# untitled.net
KiCad netlist of a schematic drawn in EAGLE
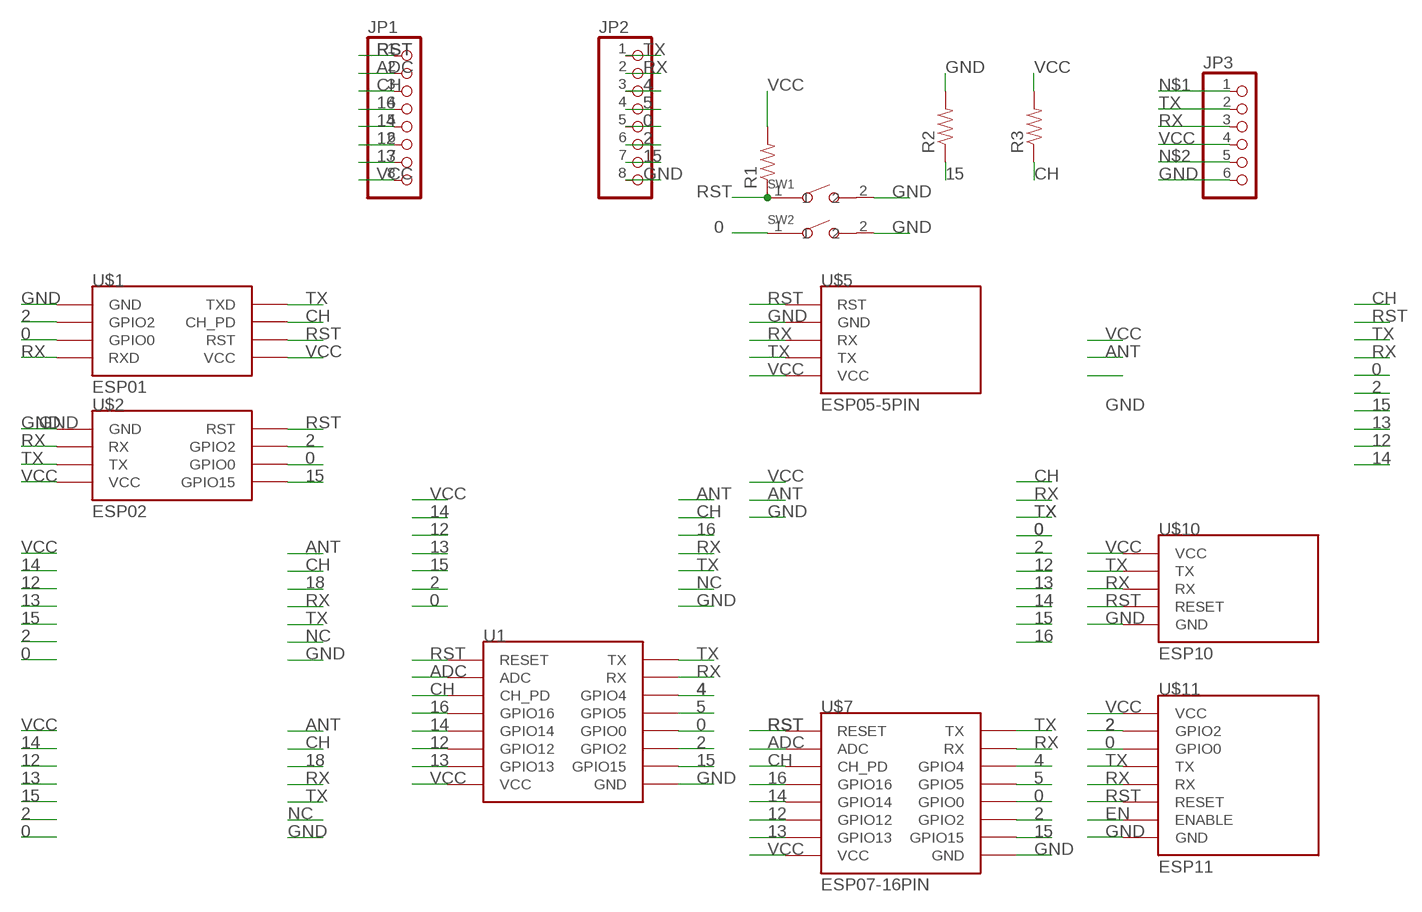
[diagram p0: schematic, sheet 1]

(export (version "E")
  (design (tool "Eeschema 10.0.6"))
  (components
    (comp (ref "JP1")
      (value "PINHD-1X8")
      (footprint "eagle-import:1X08")
      (libsource (lib "eagle-import") (part "PINHD-1X8"))
    )
    (comp (ref "JP2")
      (value "PINHD-1X8")
      (footprint "eagle-import:1X08")
      (libsource (lib "eagle-import") (part "PINHD-1X8"))
    )
    (comp (ref "JP3")
      (value "PINHD-1X6")
      (footprint "eagle-import:1X06")
      (libsource (lib "eagle-import") (part "PINHD-1X6"))
    )
    (comp (ref "R1")
      (value "RESISTOR1206")
      (footprint "eagle-import:1206")
      (libsource (lib "eagle-import") (part "RESISTOR1206"))
    )
    (comp (ref "R2")
      (value "RESISTOR1206")
      (footprint "eagle-import:1206")
      (libsource (lib "eagle-import") (part "RESISTOR1206"))
    )
    (comp (ref "R3")
      (value "RESISTOR1206")
      (footprint "eagle-import:1206")
      (libsource (lib "eagle-import") (part "RESISTOR1206"))
    )
    (comp (ref "SW1")
      (value "SMD-BUTTON(2P-6.0X3.0X2.5MM)-DHT-1163S")
      (footprint "eagle-import:SW2-4.0-6.0X3.0X2.5MM")
      (libsource (lib "eagle-import") (part "SMD-BUTTON(2P-6.0X3.0X2.5MM)-DHT-1163S"))
    )
    (comp (ref "SW2")
      (value "SMD-BUTTON(2P-6.0X3.0X2.5MM)-DHT-1163S")
      (footprint "eagle-import:SW2-4.0-6.0X3.0X2.5MM")
      (libsource (lib "eagle-import") (part "SMD-BUTTON(2P-6.0X3.0X2.5MM)-DHT-1163S"))
    )
    (comp (ref "U$1")
      (value "ESP01")
      (footprint "eagle-import:ESP01")
      (libsource (lib "eagle-import") (part "ESP01"))
    )
    (comp (ref "U$2")
      (value "ESP02")
      (footprint "eagle-import:ESP02")
      (libsource (lib "eagle-import") (part "ESP02"))
    )
    (comp (ref "U$5")
      (value "ESP05-5PIN")
      (footprint "eagle-import:ESP05-5PIN")
      (libsource (lib "eagle-import") (part "ESP05-5PIN"))
    )
    (comp (ref "U$7")
      (value "ESP07-16PIN")
      (footprint "eagle-import:ESP07-16PIN")
      (libsource (lib "eagle-import") (part "ESP07-16PIN"))
    )
    (comp (ref "U$10")
      (value "ESP10")
      (footprint "eagle-import:ESP10")
      (libsource (lib "eagle-import") (part "ESP10"))
    )
    (comp (ref "U$11")
      (value "ESP11")
      (footprint "eagle-import:ESP11")
      (libsource (lib "eagle-import") (part "ESP11"))
    )
    (comp (ref "U1")
      (value "ESP12SMD")
      (footprint "eagle-import:ESP12-SMD")
      (libsource (lib "eagle-import") (part "ESP12SMD"))
    )
  )
  (nets
    (net (code "1") (name "/0") (class "Default")
      (node (ref "JP2") (pin "5") (pinfunction "5_5") (pintype "passive"))
      (node (ref "SW2") (pin "1") (pinfunction "1_1") (pintype "bidirectional"))
      (node (ref "U$1") (pin "GPIO0") (pinfunction "GPIO0_GPIO0") (pintype "bidirectional"))
      (node (ref "U$11") (pin "P$6") (pinfunction "GPIO0_P$6") (pintype "bidirectional"))
      (node (ref "U$2") (pin "GPIO0") (pinfunction "GPIO0_GPIO0") (pintype "bidirectional"))
      (node (ref "U$7") (pin "GPIO0") (pinfunction "GPIO0_GPIO0") (pintype "bidirectional"))
      (node (ref "U1") (pin "GPIO0") (pinfunction "GPIO0_GPIO0") (pintype "bidirectional"))
    )
    (net (code "2") (name "/2") (class "Default")
      (node (ref "JP2") (pin "6") (pinfunction "6_6") (pintype "passive"))
      (node (ref "U$1") (pin "GPIO2") (pinfunction "GPIO2_GPIO2") (pintype "bidirectional"))
      (node (ref "U$11") (pin "P$7") (pinfunction "GPIO2_P$7") (pintype "bidirectional"))
      (node (ref "U$2") (pin "GPIO2") (pinfunction "GPIO2_GPIO2") (pintype "bidirectional"))
      (node (ref "U$7") (pin "GPIO2") (pinfunction "GPIO2_GPIO2") (pintype "bidirectional"))
      (node (ref "U1") (pin "GPIO2") (pinfunction "GPIO2_GPIO2") (pintype "bidirectional"))
    )
    (net (code "3") (name "/4") (class "Default")
      (node (ref "JP2") (pin "3") (pinfunction "3_3") (pintype "passive"))
      (node (ref "U$7") (pin "GPIO4") (pinfunction "GPIO4_GPIO4") (pintype "bidirectional"))
      (node (ref "U1") (pin "GPIO4") (pinfunction "GPIO4_GPIO4") (pintype "bidirectional"))
    )
    (net (code "4") (name "/5") (class "Default")
      (node (ref "JP2") (pin "4") (pinfunction "4_4") (pintype "passive"))
      (node (ref "U$7") (pin "GPIO5") (pinfunction "GPIO5_GPIO5") (pintype "bidirectional"))
      (node (ref "U1") (pin "GPIO5") (pinfunction "GPIO5_GPIO5") (pintype "bidirectional"))
    )
    (net (code "5") (name "/12") (class "Default")
      (node (ref "JP1") (pin "6") (pinfunction "6_6") (pintype "passive"))
      (node (ref "U$7") (pin "GPIO12") (pinfunction "GPIO12_GPIO12") (pintype "bidirectional"))
      (node (ref "U1") (pin "GPIO12") (pinfunction "GPIO12_GPIO12") (pintype "bidirectional"))
    )
    (net (code "6") (name "/13") (class "Default")
      (node (ref "JP1") (pin "7") (pinfunction "7_7") (pintype "passive"))
      (node (ref "U$7") (pin "GPIO13") (pinfunction "GPIO13_GPIO13") (pintype "bidirectional"))
      (node (ref "U1") (pin "GPIO13") (pinfunction "GPIO13_GPIO13") (pintype "bidirectional"))
    )
    (net (code "7") (name "/14") (class "Default")
      (node (ref "JP1") (pin "5") (pinfunction "5_5") (pintype "passive"))
      (node (ref "U$7") (pin "GPIO14") (pinfunction "GPIO14_GPIO14") (pintype "bidirectional"))
      (node (ref "U1") (pin "GPIO14") (pinfunction "GPIO14_GPIO14") (pintype "bidirectional"))
    )
    (net (code "8") (name "/15") (class "Default")
      (node (ref "JP2") (pin "7") (pinfunction "7_7") (pintype "passive"))
      (node (ref "R2") (pin "1") (pinfunction "1_1") (pintype "passive"))
      (node (ref "U$2") (pin "GPIO15/POWERDOWN") (pinfunction "GPIO15_GPIO15/POWERDOWN") (pintype "bidirectional"))
      (node (ref "U$7") (pin "GPIO15") (pinfunction "GPIO15_GPIO15") (pintype "bidirectional"))
      (node (ref "U1") (pin "GPIO15") (pinfunction "GPIO15_GPIO15") (pintype "bidirectional"))
    )
    (net (code "9") (name "/16") (class "Default")
      (node (ref "JP1") (pin "4") (pinfunction "4_4") (pintype "passive"))
      (node (ref "U$7") (pin "GPIO16") (pinfunction "GPIO16_GPIO16") (pintype "bidirectional"))
      (node (ref "U1") (pin "GPIO16") (pinfunction "GPIO16_GPIO16") (pintype "bidirectional"))
    )
    (net (code "11") (name "/ADC") (class "Default")
      (node (ref "JP1") (pin "2") (pinfunction "2_2") (pintype "passive"))
      (node (ref "U$7") (pin "ADC") (pinfunction "ADC_ADC") (pintype "bidirectional"))
      (node (ref "U1") (pin "ADC") (pinfunction "ADC_ADC") (pintype "bidirectional"))
    )
    (net (code "13") (name "/CH") (class "Default")
      (node (ref "JP1") (pin "3") (pinfunction "3_3") (pintype "passive"))
      (node (ref "R3") (pin "1") (pinfunction "1_1") (pintype "passive"))
      (node (ref "U$1") (pin "CH_PD") (pinfunction "CH_PD_CH_PD") (pintype "bidirectional"))
      (node (ref "U$7") (pin "CH_PD") (pinfunction "CH_PD_CH_PD") (pintype "bidirectional"))
      (node (ref "U1") (pin "CH_PD") (pinfunction "CH_PD_CH_PD") (pintype "bidirectional"))
    )
    (net (code "14") (name "/EN") (class "Default")
      (node (ref "U$11") (pin "P$2") (pinfunction "ENABLE_P$2") (pintype "bidirectional"))
    )
    (net (code "15") (name "/GND") (class "Default")
      (node (ref "JP2") (pin "8") (pinfunction "8_8") (pintype "passive"))
      (node (ref "JP3") (pin "6") (pinfunction "6_6") (pintype "passive"))
      (node (ref "R2") (pin "2") (pinfunction "2_2") (pintype "passive"))
      (node (ref "SW1") (pin "2") (pinfunction "2_2") (pintype "bidirectional"))
      (node (ref "SW2") (pin "2") (pinfunction "2_2") (pintype "bidirectional"))
      (node (ref "U$1") (pin "GND") (pinfunction "GND_GND") (pintype "bidirectional"))
      (node (ref "U$10") (pin "GND") (pinfunction "GND_GND") (pintype "bidirectional"))
      (node (ref "U$11") (pin "P$1") (pinfunction "GND_P$1") (pintype "bidirectional"))
      (node (ref "U$2") (pin "GND") (pinfunction "GND_GND") (pintype "bidirectional"))
      (node (ref "U$5") (pin "GND") (pinfunction "GND_GND") (pintype "bidirectional"))
      (node (ref "U$7") (pin "GND") (pinfunction "GND_GND") (pintype "bidirectional"))
      (node (ref "U1") (pin "GND") (pinfunction "GND_GND") (pintype "bidirectional"))
    )
    (net (code "16") (name "/N$1") (class "Default")
      (node (ref "JP3") (pin "1") (pinfunction "1_1") (pintype "passive"))
    )
    (net (code "17") (name "/N$2") (class "Default")
      (node (ref "JP3") (pin "5") (pinfunction "5_5") (pintype "passive"))
    )
    (net (code "19") (name "/RST") (class "Default")
      (node (ref "JP1") (pin "1") (pinfunction "1_1") (pintype "passive"))
      (node (ref "R1") (pin "1") (pinfunction "1_1") (pintype "passive"))
      (node (ref "SW1") (pin "1") (pinfunction "1_1") (pintype "bidirectional"))
      (node (ref "U$1") (pin "RST") (pinfunction "RST_RST") (pintype "bidirectional"))
      (node (ref "U$10") (pin "RESET") (pinfunction "RESET_RESET") (pintype "bidirectional"))
      (node (ref "U$11") (pin "P$3") (pinfunction "RESET_P$3") (pintype "bidirectional"))
      (node (ref "U$2") (pin "RST") (pinfunction "RST_RST") (pintype "bidirectional"))
      (node (ref "U$5") (pin "RST") (pinfunction "RST_RST") (pintype "bidirectional"))
      (node (ref "U$7") (pin "REST") (pinfunction "RESET_REST") (pintype "bidirectional"))
      (node (ref "U1") (pin "RESET") (pinfunction "RESET_RESET") (pintype "bidirectional"))
    )
    (net (code "20") (name "/RX") (class "Default")
      (node (ref "JP2") (pin "2") (pinfunction "2_2") (pintype "passive"))
      (node (ref "JP3") (pin "3") (pinfunction "3_3") (pintype "passive"))
      (node (ref "U$1") (pin "RX") (pinfunction "RXD_RX") (pintype "bidirectional"))
      (node (ref "U$10") (pin "RX") (pinfunction "RX_RX") (pintype "bidirectional"))
      (node (ref "U$11") (pin "P$4") (pinfunction "RX_P$4") (pintype "bidirectional"))
      (node (ref "U$2") (pin "RX") (pinfunction "RX_RX") (pintype "bidirectional"))
      (node (ref "U$5") (pin "RX") (pinfunction "RX_RX") (pintype "bidirectional"))
      (node (ref "U$7") (pin "RX") (pinfunction "RX_RX") (pintype "bidirectional"))
      (node (ref "U1") (pin "RXD0") (pinfunction "RX_RXD0") (pintype "bidirectional"))
    )
    (net (code "21") (name "/TX") (class "Default")
      (node (ref "JP2") (pin "1") (pinfunction "1_1") (pintype "passive"))
      (node (ref "JP3") (pin "2") (pinfunction "2_2") (pintype "passive"))
      (node (ref "U$1") (pin "TX") (pinfunction "TXD_TX") (pintype "bidirectional"))
      (node (ref "U$10") (pin "TX") (pinfunction "TX_TX") (pintype "bidirectional"))
      (node (ref "U$11") (pin "P$5") (pinfunction "TX_P$5") (pintype "bidirectional"))
      (node (ref "U$2") (pin "TX") (pinfunction "TX_TX") (pintype "bidirectional"))
      (node (ref "U$5") (pin "TX") (pinfunction "TX_TX") (pintype "bidirectional"))
      (node (ref "U$7") (pin "TX") (pinfunction "TX_TX") (pintype "bidirectional"))
      (node (ref "U1") (pin "TXD0") (pinfunction "TX_TXD0") (pintype "bidirectional"))
    )
    (net (code "22") (name "/VCC") (class "Default")
      (node (ref "JP1") (pin "8") (pinfunction "8_8") (pintype "passive"))
      (node (ref "JP3") (pin "4") (pinfunction "4_4") (pintype "passive"))
      (node (ref "R1") (pin "2") (pinfunction "2_2") (pintype "passive"))
      (node (ref "R3") (pin "2") (pinfunction "2_2") (pintype "passive"))
      (node (ref "U$1") (pin "VCC") (pinfunction "VCC_VCC") (pintype "bidirectional"))
      (node (ref "U$10") (pin "VCC") (pinfunction "VCC_VCC") (pintype "bidirectional"))
      (node (ref "U$11") (pin "P$8") (pinfunction "VCC_P$8") (pintype "bidirectional"))
      (node (ref "U$2") (pin "VCC") (pinfunction "VCC_VCC") (pintype "bidirectional"))
      (node (ref "U$5") (pin "VCC") (pinfunction "VCC_VCC") (pintype "bidirectional"))
      (node (ref "U$7") (pin "VCC") (pinfunction "VCC_VCC") (pintype "bidirectional"))
      (node (ref "U1") (pin "VCC") (pinfunction "VCC_VCC") (pintype "bidirectional"))
    )
  )
)
